# NRF51822_schematic.net
KiCad netlist of a schematic drawn in Altium Designer
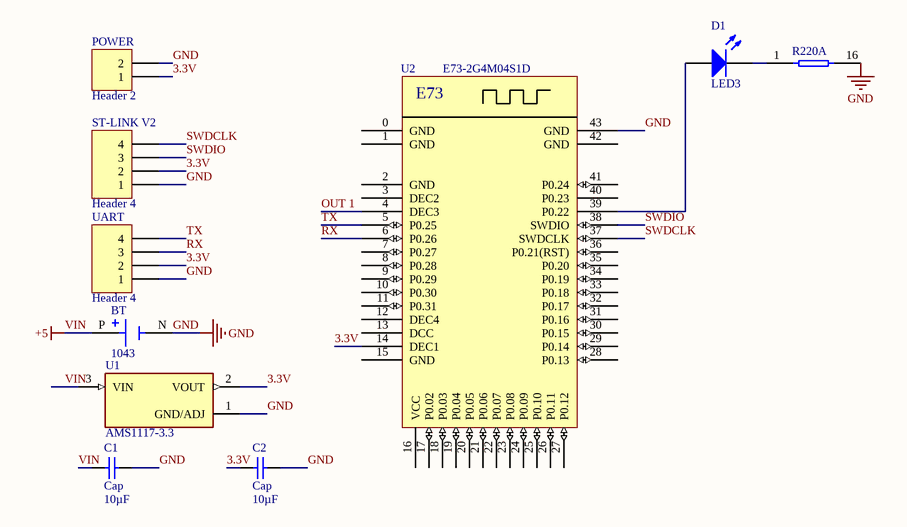
[diagram p0: NRF51822 schematic.SchDoc]

(export (version "E")
  (design (tool "Eeschema 10.0.6"))
  (components
    (comp (ref "BT")
      (value "1043")
      (footprint "BAT_1043")
      (description "THM Holder for 18650 Battery")
      (fields (field (name "MF") "Keystone Electronics"))
      (libsource (lib "1043") (part "1043"))
    )
    (comp (ref "C1")
      (value "Cap")
      (footprint "RAD-0.3")
      (description "Capacitor")
      (fields (field (name "ALTIUM_VALUE") "10µF") (field (name "PUBLISHER") "Altium Limited"))
      (libsource (lib "Miscellaneous Devices") (part "Cap"))
    )
    (comp (ref "C2")
      (value "Cap")
      (footprint "RAD-0.3")
      (description "Capacitor")
      (fields (field (name "ALTIUM_VALUE") "10µF") (field (name "PUBLISHER") "Altium Limited"))
      (libsource (lib "Miscellaneous Devices") (part "Cap"))
    )
    (comp (ref "D1")
      (value "LED3")
      (footprint "3.5X2.8X1.9")
      (description "Typical BLUE SiC LED")
      (fields (field (name "PUBLISHER") "Altium Limited"))
      (libsource (lib "Miscellaneous Devices") (part "LED3"))
    )
    (comp (ref "POWER")
      (value "Header 2")
      (footprint "HDR1X2")
      (description "Header, 2-Pin")
      (fields (field (name "PUBLISHER") "Altium Limited"))
      (libsource (lib "Miscellaneous Connectors") (part "Header 2"))
    )
    (comp (ref "R220")
      (value "Res Pack2")
      (footprint "DIP-16")
      (description "Isolated Resistor Network - Parts")
      (fields (field (name "PUBLISHER") "Altium Limited"))
      (libsource (lib "Miscellaneous Devices") (part "Res Pack2"))
    )
    (comp (ref "ST-LINK V2")
      (value "Header 4")
      (footprint "HDR1X4")
      (description "Header, 4-Pin")
      (fields (field (name "PUBLISHER") "Altium Limited"))
      (libsource (lib "Miscellaneous Connectors") (part "Header 4"))
    )
    (comp (ref "U1")
      (value "AMS1117-3.3")
      (footprint "SOT229P700X180-4N")
      (description "Sot223/Pkg 1-Amp 3.3-Volt Low Drop Out Voltage Regulatator")
      (fields (field (name "MF") "Advanced Monolithic Systems"))
      (libsource (lib "AMS1117-3.3") (part "AMS1117-3.3"))
    )
    (comp (ref "U2")
      (value "E73-2G4M04S1D")
      (footprint "E73-2G4M04S1D")
      (libsource (lib "E73-2G4M04S1D-Chengdu Ebyte Electronic Technology-Symbol-Altium-19183") (part "E73-2G4M04S1D"))
    )
    (comp (ref "UART")
      (value "Header 4")
      (footprint "HDR1X4")
      (description "Header, 4-Pin")
      (fields (field (name "PUBLISHER") "Altium Limited"))
      (libsource (lib "Miscellaneous Connectors") (part "Header 4"))
    )
  )
  (nets
    (net (code "1") (name "+5") (class "Default")
      (node (ref "BT") (pin "P") (pinfunction "POS_P") (pintype "passive"))
      (node (ref "C1") (pin "1") (pinfunction "1_1") (pintype "passive"))
      (node (ref "U1") (pin "3") (pinfunction "VIN_3") (pintype "input"))
    )
    (net (code "2") (name "/3.3V") (class "Default")
      (node (ref "C2") (pin "1") (pinfunction "1_1") (pintype "passive"))
      (node (ref "POWER") (pin "1") (pinfunction "1_1") (pintype "passive"))
      (node (ref "ST-LINK V2") (pin "2") (pinfunction "2_2") (pintype "passive"))
      (node (ref "U1") (pin "2") (pinfunction "VOUT_2") (pintype "output"))
      (node (ref "U2") (pin "14") (pinfunction "DEC1_14") (pintype "passive"))
      (node (ref "UART") (pin "2") (pinfunction "2_2") (pintype "passive"))
    )
    (net (code "4") (name "/OUT 1") (class "Default")
      (node (ref "U2") (pin "4") (pinfunction "DEC3_4") (pintype "passive"))
    )
    (net (code "5") (name "/RX") (class "Default")
      (node (ref "U2") (pin "6") (pinfunction "P0.26_6") (pintype "bidirectional"))
      (node (ref "UART") (pin "3") (pinfunction "3_3") (pintype "passive"))
    )
    (net (code "6") (name "/SWDCLK") (class "Default")
      (node (ref "ST-LINK V2") (pin "4") (pinfunction "4_4") (pintype "passive"))
      (node (ref "U2") (pin "37") (pinfunction "SWDCLK_37") (pintype "bidirectional"))
    )
    (net (code "7") (name "/SWDIO") (class "Default")
      (node (ref "ST-LINK V2") (pin "3") (pinfunction "3_3") (pintype "passive"))
      (node (ref "U2") (pin "38") (pinfunction "SWDIO_38") (pintype "bidirectional"))
    )
    (net (code "8") (name "/TX") (class "Default")
      (node (ref "U2") (pin "5") (pinfunction "P0.25_5") (pintype "bidirectional"))
      (node (ref "UART") (pin "4") (pinfunction "4_4") (pintype "passive"))
    )
    (net (code "9") (name "GND") (class "Default")
      (node (ref "BT") (pin "N") (pinfunction "NEG_N") (pintype "passive"))
      (node (ref "C1") (pin "2") (pinfunction "2_2") (pintype "passive"))
      (node (ref "C2") (pin "2") (pinfunction "2_2") (pintype "passive"))
      (node (ref "POWER") (pin "2") (pinfunction "2_2") (pintype "passive"))
      (node (ref "R220") (pin "16") (pinfunction "16_16") (pintype "passive"))
      (node (ref "ST-LINK V2") (pin "1") (pinfunction "1_1") (pintype "passive"))
      (node (ref "U1") (pin "1") (pinfunction "GND/ADJ_1") (pintype "power_in"))
      (node (ref "U2") (pin "43") (pinfunction "GND_43") (pintype "passive"))
      (node (ref "UART") (pin "1") (pinfunction "1_1") (pintype "passive"))
    )
    (net (code "10") (name "Net-(D1-A)") (class "Default")
      (node (ref "D1") (pin "1") (pinfunction "A_1") (pintype "passive"))
      (node (ref "U2") (pin "39") (pinfunction "P0.22_39") (pintype "passive"))
    )
    (net (code "11") (name "Net-(D1-K)") (class "Default")
      (node (ref "D1") (pin "2") (pinfunction "K_2") (pintype "passive"))
      (node (ref "R220") (pin "1") (pinfunction "1_1") (pintype "passive"))
    )
    (net (code "12") (name "unconnected-(U2-DCC-Pad13)") (class "Default")
      (node (ref "U2") (pin "13") (pinfunction "DCC_13") (pintype "passive"))
    )
    (net (code "13") (name "unconnected-(U2-DEC2-Pad3)") (class "Default")
      (node (ref "U2") (pin "3") (pinfunction "DEC2_3") (pintype "passive"))
    )
    (net (code "14") (name "unconnected-(U2-DEC4-Pad12)") (class "Default")
      (node (ref "U2") (pin "12") (pinfunction "DEC4_12") (pintype "passive"))
    )
    (net (code "15") (name "unconnected-(U2-GND-Pad0)") (class "Default")
      (node (ref "U2") (pin "0") (pinfunction "GND_0") (pintype "passive"))
    )
    (net (code "16") (name "unconnected-(U2-GND-Pad1)") (class "Default")
      (node (ref "U2") (pin "1") (pinfunction "GND_1") (pintype "passive"))
    )
    (net (code "17") (name "unconnected-(U2-GND-Pad2)") (class "Default")
      (node (ref "U2") (pin "2") (pinfunction "GND_2") (pintype "passive"))
    )
    (net (code "18") (name "unconnected-(U2-GND-Pad15)") (class "Default")
      (node (ref "U2") (pin "15") (pinfunction "GND_15") (pintype "passive"))
    )
    (net (code "19") (name "unconnected-(U2-GND-Pad42)") (class "Default")
      (node (ref "U2") (pin "42") (pinfunction "GND_42") (pintype "passive"))
    )
    (net (code "20") (name "unconnected-(U2-P0.02-Pad17)") (class "Default")
      (node (ref "U2") (pin "17") (pinfunction "P0.02_17") (pintype "bidirectional"))
    )
    (net (code "21") (name "unconnected-(U2-P0.03-Pad18)") (class "Default")
      (node (ref "U2") (pin "18") (pinfunction "P0.03_18") (pintype "bidirectional"))
    )
    (net (code "22") (name "unconnected-(U2-P0.04-Pad19)") (class "Default")
      (node (ref "U2") (pin "19") (pinfunction "P0.04_19") (pintype "bidirectional"))
    )
    (net (code "23") (name "unconnected-(U2-P0.05-Pad20)") (class "Default")
      (node (ref "U2") (pin "20") (pinfunction "P0.05_20") (pintype "bidirectional"))
    )
    (net (code "24") (name "unconnected-(U2-P0.06-Pad21)") (class "Default")
      (node (ref "U2") (pin "21") (pinfunction "P0.06_21") (pintype "bidirectional"))
    )
    (net (code "25") (name "unconnected-(U2-P0.07-Pad22)") (class "Default")
      (node (ref "U2") (pin "22") (pinfunction "P0.07_22") (pintype "bidirectional"))
    )
    (net (code "26") (name "unconnected-(U2-P0.08-Pad23)") (class "Default")
      (node (ref "U2") (pin "23") (pinfunction "P0.08_23") (pintype "bidirectional"))
    )
    (net (code "27") (name "unconnected-(U2-P0.09-Pad24)") (class "Default")
      (node (ref "U2") (pin "24") (pinfunction "P0.09_24") (pintype "bidirectional"))
    )
    (net (code "28") (name "unconnected-(U2-P0.10-Pad25)") (class "Default")
      (node (ref "U2") (pin "25") (pinfunction "P0.10_25") (pintype "bidirectional"))
    )
    (net (code "29") (name "unconnected-(U2-P0.11-Pad26)") (class "Default")
      (node (ref "U2") (pin "26") (pinfunction "P0.11_26") (pintype "bidirectional"))
    )
    (net (code "30") (name "unconnected-(U2-P0.12-Pad27)") (class "Default")
      (node (ref "U2") (pin "27") (pinfunction "P0.12_27") (pintype "bidirectional"))
    )
    (net (code "31") (name "unconnected-(U2-P0.13-Pad28)") (class "Default")
      (node (ref "U2") (pin "28") (pinfunction "P0.13_28") (pintype "bidirectional"))
    )
    (net (code "32") (name "unconnected-(U2-P0.14-Pad29)") (class "Default")
      (node (ref "U2") (pin "29") (pinfunction "P0.14_29") (pintype "bidirectional"))
    )
    (net (code "33") (name "unconnected-(U2-P0.15-Pad30)") (class "Default")
      (node (ref "U2") (pin "30") (pinfunction "P0.15_30") (pintype "bidirectional"))
    )
    (net (code "34") (name "unconnected-(U2-P0.16-Pad31)") (class "Default")
      (node (ref "U2") (pin "31") (pinfunction "P0.16_31") (pintype "bidirectional"))
    )
    (net (code "35") (name "unconnected-(U2-P0.17-Pad32)") (class "Default")
      (node (ref "U2") (pin "32") (pinfunction "P0.17_32") (pintype "bidirectional"))
    )
    (net (code "36") (name "unconnected-(U2-P0.18-Pad33)") (class "Default")
      (node (ref "U2") (pin "33") (pinfunction "P0.18_33") (pintype "bidirectional"))
    )
    (net (code "37") (name "unconnected-(U2-P0.19-Pad34)") (class "Default")
      (node (ref "U2") (pin "34") (pinfunction "P0.19_34") (pintype "bidirectional"))
    )
    (net (code "38") (name "unconnected-(U2-P0.20-Pad35)") (class "Default")
      (node (ref "U2") (pin "35") (pinfunction "P0.20_35") (pintype "bidirectional"))
    )
    (net (code "39") (name "unconnected-(U2-P0.21(RST)-Pad36)") (class "Default")
      (node (ref "U2") (pin "36") (pinfunction "P0.21(RST)_36") (pintype "bidirectional"))
    )
    (net (code "40") (name "unconnected-(U2-P0.23-Pad40)") (class "Default")
      (node (ref "U2") (pin "40") (pinfunction "P0.23_40") (pintype "passive"))
    )
    (net (code "41") (name "unconnected-(U2-P0.24-Pad41)") (class "Default")
      (node (ref "U2") (pin "41") (pinfunction "P0.24_41") (pintype "bidirectional"))
    )
    (net (code "42") (name "unconnected-(U2-P0.27-Pad7)") (class "Default")
      (node (ref "U2") (pin "7") (pinfunction "P0.27_7") (pintype "bidirectional"))
    )
    (net (code "43") (name "unconnected-(U2-P0.28-Pad8)") (class "Default")
      (node (ref "U2") (pin "8") (pinfunction "P0.28_8") (pintype "bidirectional"))
    )
    (net (code "44") (name "unconnected-(U2-P0.29-Pad9)") (class "Default")
      (node (ref "U2") (pin "9") (pinfunction "P0.29_9") (pintype "bidirectional"))
    )
    (net (code "45") (name "unconnected-(U2-P0.30-Pad10)") (class "Default")
      (node (ref "U2") (pin "10") (pinfunction "P0.30_10") (pintype "bidirectional"))
    )
    (net (code "46") (name "unconnected-(U2-P0.31-Pad11)") (class "Default")
      (node (ref "U2") (pin "11") (pinfunction "P0.31_11") (pintype "bidirectional"))
    )
    (net (code "47") (name "unconnected-(U2-VCC-Pad16)") (class "Default")
      (node (ref "U2") (pin "16") (pinfunction "VCC_16") (pintype "passive"))
    )
  )
)
